# AQCA-Light-Control-uC-A1.net
KiCad netlist of a schematic drawn in Altium Designer
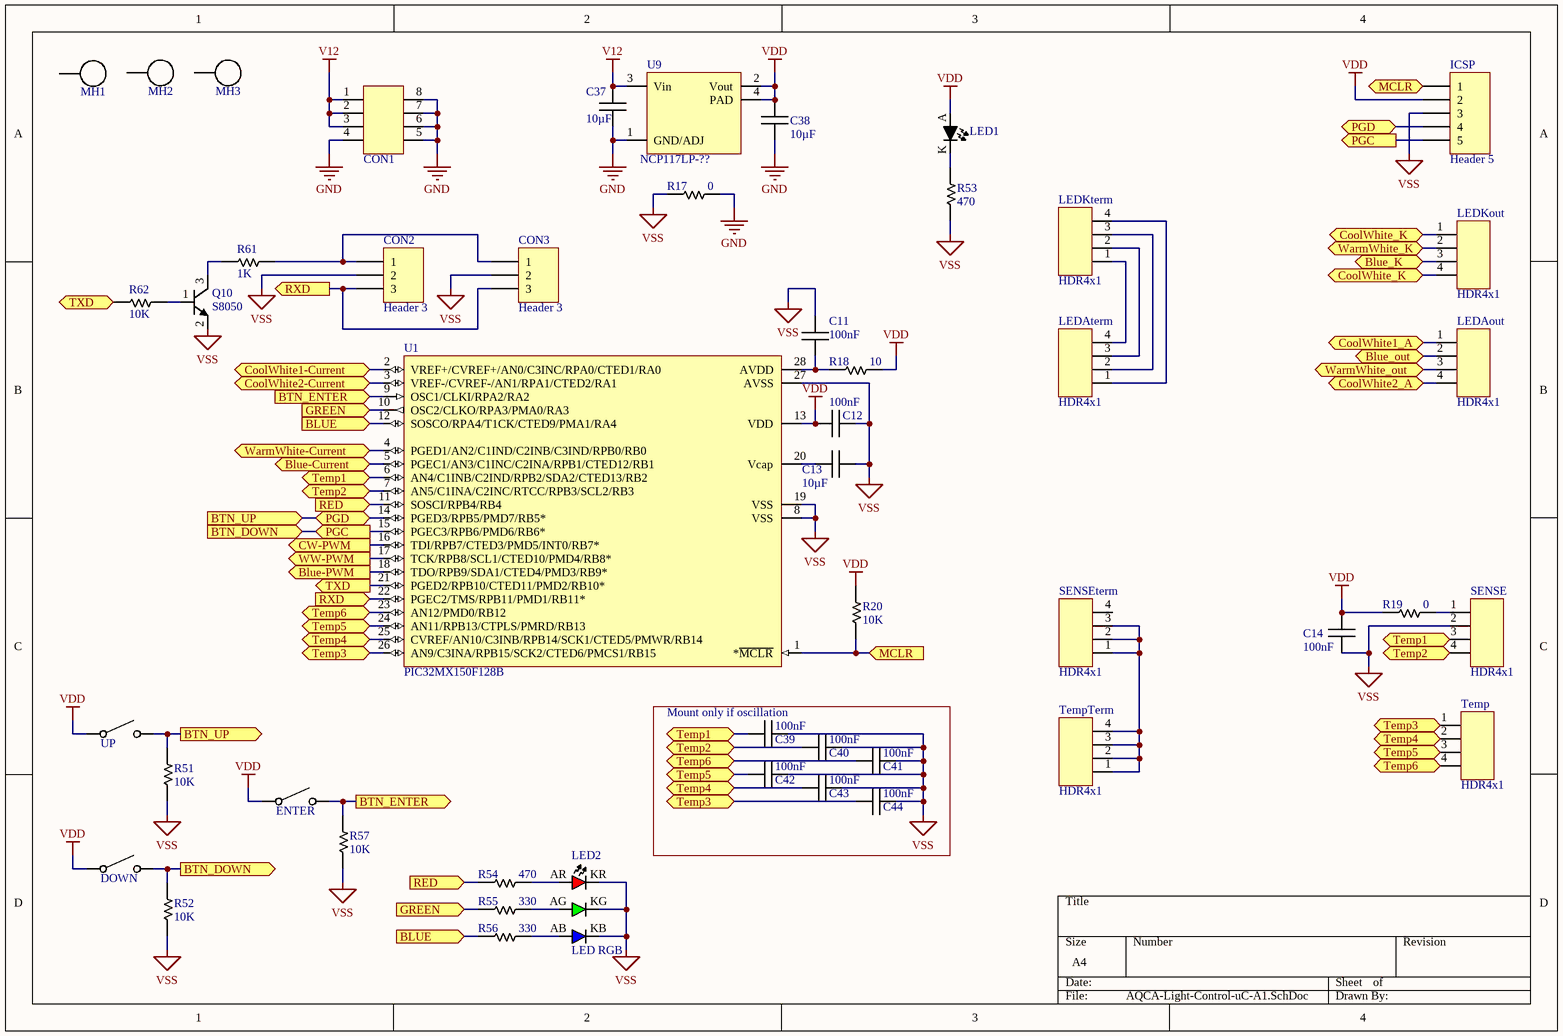
[diagram p0: AQCA-Light-Control-uC-A1.SchDoc]

(export (version "E")
  (design (tool "Eeschema 10.0.6"))
  (components
    (comp (ref "C11")
      (value "100nF")
      (footprint "CAPC1608N")
      (fields (field (name "VOLTAGE") "16V"))
      (libsource (lib "Megaxone") (part "Capacitor"))
    )
    (comp (ref "C12")
      (value "100nF")
      (footprint "CAPC1608N")
      (fields (field (name "VOLTAGE") "16V"))
      (libsource (lib "Megaxone") (part "Capacitor"))
    )
    (comp (ref "C13")
      (value "10µF")
      (footprint "CAPC2012N")
      (fields (field (name "VOLTAGE") "16V"))
      (libsource (lib "Megaxone") (part "Capacitor"))
    )
    (comp (ref "C14")
      (value "100nF")
      (footprint "CAPC1608N")
      (fields (field (name "VOLTAGE") "16V"))
      (libsource (lib "Megaxone") (part "Capacitor"))
    )
    (comp (ref "C37")
      (value "10µF")
      (footprint "CAPC3225N")
      (fields (field (name "VOLTAGE") "25V"))
      (libsource (lib "Megaxone") (part "Capacitor"))
    )
    (comp (ref "C38")
      (value "10µF")
      (footprint "CAPC3225N")
      (fields (field (name "VOLTAGE") "25V"))
      (libsource (lib "Megaxone") (part "Capacitor"))
    )
    (comp (ref "C39")
      (value "100nF")
      (footprint "CAPC1608N")
      (fields (field (name "VOLTAGE") "16V"))
      (libsource (lib "Megaxone") (part "Capacitor"))
    )
    (comp (ref "C40")
      (value "100nF")
      (footprint "CAPC1608N")
      (fields (field (name "VOLTAGE") "16V"))
      (libsource (lib "Megaxone") (part "Capacitor"))
    )
    (comp (ref "C41")
      (value "100nF")
      (footprint "CAPC1608N")
      (fields (field (name "VOLTAGE") "16V"))
      (libsource (lib "Megaxone") (part "Capacitor"))
    )
    (comp (ref "C42")
      (value "100nF")
      (footprint "CAPC1608N")
      (fields (field (name "VOLTAGE") "16V"))
      (libsource (lib "Megaxone") (part "Capacitor"))
    )
    (comp (ref "C43")
      (value "100nF")
      (footprint "CAPC1608N")
      (fields (field (name "VOLTAGE") "16V"))
      (libsource (lib "Megaxone") (part "Capacitor"))
    )
    (comp (ref "C44")
      (value "100nF")
      (footprint "CAPC1608N")
      (fields (field (name "VOLTAGE") "16V"))
      (libsource (lib "Megaxone") (part "Capacitor"))
    )
    (comp (ref "CON1")
      (value "Molex Mini-Fit 8pin")
      (footprint "Molex Mini-Fit 8pin")
      (libsource (lib "Megaxone") (part "Molex Mini-Fit 8pin"))
    )
    (comp (ref "CON2")
      (value "Header 3")
      (footprint "HDR1X3")
      (description "Header, 3-Pin")
      (fields (field (name "PUBLISHER") "Altium Limited"))
      (libsource (lib "Miscellaneous Connectors") (part "Header 3"))
    )
    (comp (ref "CON3")
      (value "Header 3")
      (footprint "HDR1X3")
      (description "Header, 3-Pin")
      (fields (field (name "PUBLISHER") "Altium Limited"))
      (libsource (lib "Miscellaneous Connectors") (part "Header 3"))
    )
    (comp (ref "DOWN")
      (value "Tact Button NO")
      (footprint "TACT SMD 4.5×4.5mm")
      (libsource (lib "Megaxone") (part "Tact Button NO"))
    )
    (comp (ref "ENTER")
      (value "Tact Button NO")
      (footprint "TACT SMD 4.5×4.5mm")
      (libsource (lib "Megaxone") (part "Tact Button NO"))
    )
    (comp (ref "ICSP")
      (value "Header 5")
      (footprint "HDR1X5")
      (description "Header, 5-Pin")
      (fields (field (name "PUBLISHER") "Altium Limited"))
      (libsource (lib "Miscellaneous Connectors") (part "Header 5"))
    )
    (comp (ref "LED1") (value "~") (footprint "LED 3216m") (libsource (lib "Megaxone") (part "LED")))
    (comp (ref "LED2")
      (value "LED RGB")
      (footprint "LED PLCC-6")
      (libsource (lib "Megaxone") (part "LED RGB"))
    )
    (comp (ref "LEDAout")
      (value "HDR4x1")
      (footprint "HDR4x1 EDGE female")
      (libsource (lib "") (part "HDR4x1_1"))
    )
    (comp (ref "LEDAterm")
      (value "HDR4x1")
      (footprint "HDR4x1 EDGE male")
      (libsource (lib "Megaxone") (part "HDR4x1"))
    )
    (comp (ref "LEDKout")
      (value "HDR4x1")
      (footprint "HDR4x1 EDGE female")
      (libsource (lib "") (part "HDR4x1_1"))
    )
    (comp (ref "LEDKterm")
      (value "HDR4x1")
      (footprint "HDR4x1 EDGE male")
      (libsource (lib "Megaxone") (part "HDR4x1"))
    )
    (comp (ref "MH1")
      (value "Mounting Hole")
      (footprint "Mount Hole 4-6.5")
      (libsource (lib "Megaxone") (part "Mounting Hole"))
    )
    (comp (ref "MH2")
      (value "Mounting Hole")
      (footprint "Mount Hole 4-6.5")
      (libsource (lib "Megaxone") (part "Mounting Hole"))
    )
    (comp (ref "MH3")
      (value "Mounting Hole")
      (footprint "Mount Hole 4-6.5")
      (libsource (lib "Megaxone") (part "Mounting Hole"))
    )
    (comp (ref "Q10") (value "S8050") (footprint "SOT23_N") (libsource (lib "Megaxone") (part "NPN")))
    (comp (ref "R17") (value "0") (footprint "RESC1608N") (libsource (lib "Megaxone") (part "Resistor")))
    (comp (ref "R18") (value "10") (footprint "RESC1608N") (libsource (lib "Megaxone") (part "Resistor")))
    (comp (ref "R19") (value "0") (footprint "RESC1608N") (libsource (lib "Megaxone") (part "Resistor")))
    (comp (ref "R20") (value "10K") (footprint "RESC1608N") (libsource (lib "") (part "Resistor_1")))
    (comp (ref "R51") (value "10K") (footprint "RESC1608N") (libsource (lib "") (part "Resistor_1")))
    (comp (ref "R52") (value "10K") (footprint "RESC1608N") (libsource (lib "") (part "Resistor_1")))
    (comp (ref "R53") (value "470") (footprint "RESC1608N") (libsource (lib "") (part "Resistor_1")))
    (comp (ref "R54") (value "470") (footprint "RESC1608N") (libsource (lib "Megaxone") (part "Resistor")))
    (comp (ref "R55") (value "330") (footprint "RESC1608N") (libsource (lib "Megaxone") (part "Resistor")))
    (comp (ref "R56") (value "330") (footprint "RESC1608N") (libsource (lib "Megaxone") (part "Resistor")))
    (comp (ref "R57") (value "10K") (footprint "RESC1608N") (libsource (lib "") (part "Resistor_1")))
    (comp (ref "R61") (value "1K") (footprint "RESC1608N") (libsource (lib "Megaxone") (part "Resistor")))
    (comp (ref "R62") (value "10K") (footprint "RESC1608N") (libsource (lib "Megaxone") (part "Resistor")))
    (comp (ref "SENSE")
      (value "HDR4x1")
      (footprint "HDR4x1 EDGE female")
      (libsource (lib "") (part "HDR4x1_1"))
    )
    (comp (ref "SENSEterm")
      (value "HDR4x1")
      (footprint "HDR4x1 EDGE male")
      (libsource (lib "Megaxone") (part "HDR4x1"))
    )
    (comp (ref "Temp")
      (value "HDR4x1")
      (footprint "HDR4x1 EDGE female")
      (libsource (lib "") (part "HDR4x1_1"))
    )
    (comp (ref "TempTerm")
      (value "HDR4x1")
      (footprint "HDR4x1 EDGE male")
      (libsource (lib "Megaxone") (part "HDR4x1"))
    )
    (comp (ref "U1")
      (value "PIC32MX150F128B")
      (footprint "SSOP28_N")
      (libsource (lib "Megaxone") (part "PIC32MX120FxxxB"))
    )
    (comp (ref "U9")
      (value "NCP117LP-??")
      (footprint "SOT223-4N")
      (libsource (lib "Megaxone") (part "NCP1117LP"))
    )
    (comp (ref "UP")
      (value "Tact Button NO")
      (footprint "TACT SMD 4.5×4.5mm")
      (libsource (lib "Megaxone") (part "Tact Button NO"))
    )
  )
  (nets
    (net (code "1") (name "/BLUE") (class "Default")
      (node (ref "R56") (pin "1") (pinfunction "1_1") (pintype "passive"))
      (node (ref "U1") (pin "12") (pinfunction "SOSCO/RPA4/T1CK/CTED9/PMA1/RA4_12") (pintype "bidirectional"))
    )
    (net (code "2") (name "/BTN_DOWN") (class "Default")
      (node (ref "DOWN") (pin "2") (pinfunction "2_2") (pintype "passive"))
      (node (ref "ICSP") (pin "5") (pinfunction "5_5") (pintype "passive"))
      (node (ref "R52") (pin "2") (pinfunction "2_2") (pintype "passive"))
      (node (ref "U1") (pin "15") (pinfunction "PGEC3/RPB6/PMD6/RB6*_15") (pintype "bidirectional"))
    )
    (net (code "3") (name "/BTN_ENTER") (class "Default")
      (node (ref "ENTER") (pin "2") (pinfunction "2_2") (pintype "passive"))
      (node (ref "R57") (pin "2") (pinfunction "2_2") (pintype "passive"))
      (node (ref "U1") (pin "9") (pinfunction "OSC1/CLKI/RPA2/RA2_9") (pintype "input"))
    )
    (net (code "4") (name "/BTN_UP") (class "Default")
      (node (ref "ICSP") (pin "4") (pinfunction "4_4") (pintype "passive"))
      (node (ref "R51") (pin "2") (pinfunction "2_2") (pintype "passive"))
      (node (ref "U1") (pin "14") (pinfunction "PGED3/RPB5/PMD7/RB5*_14") (pintype "bidirectional"))
      (node (ref "UP") (pin "2") (pinfunction "2_2") (pintype "passive"))
    )
    (net (code "5") (name "/Blue-Current") (class "Default")
      (node (ref "U1") (pin "5") (pinfunction "PGEC1/AN3/C1INC/C2INA/RPB1/CTED12/RB1_5") (pintype "bidirectional"))
    )
    (net (code "6") (name "/Blue-PWM") (class "Default")
      (node (ref "U1") (pin "18") (pinfunction "TDO/RPB9/SDA1/CTED4/PMD3/RB9*_18") (pintype "bidirectional"))
    )
    (net (code "7") (name "/Blue_K") (class "Default")
      (node (ref "LEDKout") (pin "3") (pinfunction "3_3") (pintype "passive"))
    )
    (net (code "8") (name "/Blue_out") (class "Default")
      (node (ref "LEDAout") (pin "2") (pinfunction "2_2") (pintype "passive"))
    )
    (net (code "9") (name "/CW-PWM") (class "Default")
      (node (ref "U1") (pin "16") (pinfunction "TDI/RPB7/CTED3/PMD5/INT0/RB7*_16") (pintype "bidirectional"))
    )
    (net (code "10") (name "/CoolWhite1-Current") (class "Default")
      (node (ref "U1") (pin "2") (pinfunction "VREF+/CVREF+/AN0/C3INC/RPA0/CTED1/RA0_2") (pintype "bidirectional"))
    )
    (net (code "11") (name "/CoolWhite1_A") (class "Default")
      (node (ref "LEDAout") (pin "1") (pinfunction "1_1") (pintype "passive"))
    )
    (net (code "12") (name "/CoolWhite2-Current") (class "Default")
      (node (ref "U1") (pin "3") (pinfunction "VREF-/CVREF-/AN1/RPA1/CTED2/RA1_3") (pintype "bidirectional"))
    )
    (net (code "13") (name "/CoolWhite2_A") (class "Default")
      (node (ref "LEDAout") (pin "4") (pinfunction "4_4") (pintype "passive"))
    )
    (net (code "14") (name "/CoolWhite_K") (class "Default")
      (node (ref "LEDKout") (pin "1") (pinfunction "1_1") (pintype "passive"))
      (node (ref "LEDKout") (pin "4") (pinfunction "4_4") (pintype "passive"))
    )
    (net (code "15") (name "/GREEN") (class "Default")
      (node (ref "R55") (pin "1") (pinfunction "1_1") (pintype "passive"))
      (node (ref "U1") (pin "10") (pinfunction "OSC2/CLKO/RPA3/PMA0/RA3_10") (pintype "output"))
    )
    (net (code "16") (name "/MCLR") (class "Default")
      (node (ref "ICSP") (pin "1") (pinfunction "1_1") (pintype "passive"))
      (node (ref "R20") (pin "1") (pinfunction "1_1") (pintype "passive"))
      (node (ref "U1") (pin "1") (pinfunction "*~{MCLR}_1") (pintype "input"))
    )
    (net (code "17") (name "/RED") (class "Default")
      (node (ref "R54") (pin "1") (pinfunction "1_1") (pintype "passive"))
      (node (ref "U1") (pin "11") (pinfunction "SOSCI/RPB4/RB4_11") (pintype "bidirectional"))
    )
    (net (code "18") (name "/RXD") (class "Default")
      (node (ref "CON2") (pin "3") (pinfunction "3_3") (pintype "passive"))
      (node (ref "CON3") (pin "3") (pinfunction "3_3") (pintype "passive"))
      (node (ref "U1") (pin "22") (pinfunction "PGEC2/TMS/RPB11/PMD1/RB11*_22") (pintype "bidirectional"))
    )
    (net (code "19") (name "/TXD") (class "Default")
      (node (ref "R62") (pin "1") (pinfunction "1_1") (pintype "passive"))
      (node (ref "U1") (pin "21") (pinfunction "PGED2/RPB10/CTED11/PMD2/RB10*_21") (pintype "bidirectional"))
    )
    (net (code "20") (name "/Temp1") (class "Default")
      (node (ref "C39") (pin "1") (pinfunction "1_1") (pintype "passive"))
      (node (ref "SENSE") (pin "3") (pinfunction "3_3") (pintype "passive"))
      (node (ref "U1") (pin "6") (pinfunction "AN4/C1INB/C2IND/RPB2/SDA2/CTED13/RB2_6") (pintype "bidirectional"))
    )
    (net (code "21") (name "/Temp2") (class "Default")
      (node (ref "C40") (pin "1") (pinfunction "1_1") (pintype "passive"))
      (node (ref "SENSE") (pin "4") (pinfunction "4_4") (pintype "passive"))
      (node (ref "U1") (pin "7") (pinfunction "AN5/C1INA/C2INC/RTCC/RPB3/SCL2/RB3_7") (pintype "bidirectional"))
    )
    (net (code "22") (name "/Temp3") (class "Default")
      (node (ref "C44") (pin "1") (pinfunction "1_1") (pintype "passive"))
      (node (ref "Temp") (pin "1") (pinfunction "1_1") (pintype "passive"))
      (node (ref "U1") (pin "26") (pinfunction "AN9/C3INA/RPB15/SCK2/CTED6/PMCS1/RB15_26") (pintype "bidirectional"))
    )
    (net (code "23") (name "/Temp4") (class "Default")
      (node (ref "C43") (pin "1") (pinfunction "1_1") (pintype "passive"))
      (node (ref "Temp") (pin "2") (pinfunction "2_2") (pintype "passive"))
      (node (ref "U1") (pin "25") (pinfunction "CVREF/AN10/C3INB/RPB14/SCK1/CTED5/PMWR/RB14_25") (pintype "bidirectional"))
    )
    (net (code "24") (name "/Temp5") (class "Default")
      (node (ref "C42") (pin "1") (pinfunction "1_1") (pintype "passive"))
      (node (ref "Temp") (pin "3") (pinfunction "3_3") (pintype "passive"))
      (node (ref "U1") (pin "24") (pinfunction "AN11/RPB13/CTPLS/PMRD/RB13_24") (pintype "bidirectional"))
    )
    (net (code "25") (name "/Temp6") (class "Default")
      (node (ref "C41") (pin "1") (pinfunction "1_1") (pintype "passive"))
      (node (ref "Temp") (pin "4") (pinfunction "4_4") (pintype "passive"))
      (node (ref "U1") (pin "23") (pinfunction "AN12/PMD0/RB12_23") (pintype "bidirectional"))
    )
    (net (code "26") (name "/WW-PWM") (class "Default")
      (node (ref "U1") (pin "17") (pinfunction "TCK/RPB8/SCL1/CTED10/PMD4/RB8*_17") (pintype "bidirectional"))
    )
    (net (code "27") (name "/WarmWhite-Current") (class "Default")
      (node (ref "U1") (pin "4") (pinfunction "PGED1/AN2/C1IND/C2INB/C3IND/RPB0/RB0_4") (pintype "bidirectional"))
    )
    (net (code "28") (name "/WarmWhite_K") (class "Default")
      (node (ref "LEDKout") (pin "2") (pinfunction "2_2") (pintype "passive"))
    )
    (net (code "29") (name "/WarmWhite_out") (class "Default")
      (node (ref "LEDAout") (pin "3") (pinfunction "3_3") (pintype "passive"))
    )
    (net (code "30") (name "GND") (class "Default")
      (node (ref "C37") (pin "1") (pinfunction "1_1") (pintype "passive"))
      (node (ref "C38") (pin "1") (pinfunction "1_1") (pintype "passive"))
      (node (ref "CON1") (pin "4") (pintype "power_in"))
      (node (ref "CON1") (pin "5") (pintype "power_in"))
      (node (ref "CON1") (pin "6") (pintype "power_in"))
      (node (ref "CON1") (pin "7") (pintype "power_in"))
      (node (ref "CON1") (pin "8") (pintype "power_in"))
      (node (ref "R17") (pin "2") (pinfunction "2_2") (pintype "passive"))
      (node (ref "U9") (pin "1") (pinfunction "GND/ADJ_1") (pintype "power_in"))
    )
    (net (code "31") (name "Net-(CON2-Pad1)") (class "Default")
      (node (ref "CON2") (pin "1") (pinfunction "1_1") (pintype "passive"))
      (node (ref "CON3") (pin "1") (pinfunction "1_1") (pintype "passive"))
      (node (ref "R61") (pin "2") (pinfunction "2_2") (pintype "passive"))
    )
    (net (code "32") (name "Net-(LED1-PadK)") (class "Default")
      (node (ref "LED1") (pin "K") (pinfunction "K_K") (pintype "passive"))
      (node (ref "R53") (pin "2") (pinfunction "2_2") (pintype "passive"))
    )
    (net (code "33") (name "Net-(LED2-PadAB)") (class "Default")
      (node (ref "LED2") (pin "AB") (pinfunction "AB_AB") (pintype "passive"))
      (node (ref "R56") (pin "2") (pinfunction "2_2") (pintype "passive"))
    )
    (net (code "34") (name "Net-(LED2-PadAG)") (class "Default")
      (node (ref "LED2") (pin "AG") (pinfunction "AG_AG") (pintype "passive"))
      (node (ref "R55") (pin "2") (pinfunction "2_2") (pintype "passive"))
    )
    (net (code "35") (name "Net-(LED2-PadAR)") (class "Default")
      (node (ref "LED2") (pin "AR") (pinfunction "AR_AR") (pintype "passive"))
      (node (ref "R54") (pin "2") (pinfunction "2_2") (pintype "passive"))
    )
    (net (code "36") (name "Net-(LEDAterm-Pad1)") (class "Default")
      (node (ref "LEDAterm") (pin "1") (pinfunction "1_1") (pintype "passive"))
      (node (ref "LEDKterm") (pin "4") (pinfunction "4_4") (pintype "passive"))
    )
    (net (code "37") (name "Net-(LEDAterm-Pad2)") (class "Default")
      (node (ref "LEDAterm") (pin "2") (pinfunction "2_2") (pintype "passive"))
      (node (ref "LEDKterm") (pin "3") (pinfunction "3_3") (pintype "passive"))
    )
    (net (code "38") (name "Net-(LEDAterm-Pad3)") (class "Default")
      (node (ref "LEDAterm") (pin "3") (pinfunction "3_3") (pintype "passive"))
      (node (ref "LEDKterm") (pin "2") (pinfunction "2_2") (pintype "passive"))
    )
    (net (code "39") (name "Net-(LEDAterm-Pad4)") (class "Default")
      (node (ref "LEDAterm") (pin "4") (pinfunction "4_4") (pintype "passive"))
      (node (ref "LEDKterm") (pin "1") (pinfunction "1_1") (pintype "passive"))
    )
    (net (code "40") (name "Net-(Q10-B)") (class "Default")
      (node (ref "Q10") (pin "1") (pinfunction "B_1") (pintype "passive"))
      (node (ref "R62") (pin "2") (pinfunction "2_2") (pintype "passive"))
    )
    (net (code "41") (name "Net-(Q10-C)") (class "Default")
      (node (ref "Q10") (pin "3") (pinfunction "C_3") (pintype "passive"))
      (node (ref "R61") (pin "1") (pinfunction "1_1") (pintype "passive"))
    )
    (net (code "42") (name "Net-(R19-Pad2)") (class "Default")
      (node (ref "R19") (pin "2") (pinfunction "2_2") (pintype "passive"))
      (node (ref "SENSE") (pin "1") (pinfunction "1_1") (pintype "passive"))
    )
    (net (code "43") (name "Net-(SENSEterm-Pad1)") (class "Default")
      (node (ref "SENSEterm") (pin "1") (pinfunction "1_1") (pintype "passive"))
      (node (ref "SENSEterm") (pin "2") (pinfunction "2_2") (pintype "passive"))
      (node (ref "SENSEterm") (pin "3") (pinfunction "3_3") (pintype "passive"))
      (node (ref "TempTerm") (pin "1") (pinfunction "1_1") (pintype "passive"))
      (node (ref "TempTerm") (pin "2") (pinfunction "2_2") (pintype "passive"))
      (node (ref "TempTerm") (pin "3") (pinfunction "3_3") (pintype "passive"))
      (node (ref "TempTerm") (pin "4") (pinfunction "4_4") (pintype "passive"))
    )
    (net (code "44") (name "Net-(U1-AVDD)") (class "Default")
      (node (ref "C11") (pin "1") (pinfunction "1_1") (pintype "passive"))
      (node (ref "R18") (pin "1") (pinfunction "1_1") (pintype "passive"))
      (node (ref "U1") (pin "28") (pinfunction "AVDD_28") (pintype "power_in"))
    )
    (net (code "45") (name "Net-(U1-Vcap)") (class "Default")
      (node (ref "C13") (pin "1") (pinfunction "1_1") (pintype "passive"))
      (node (ref "U1") (pin "20") (pinfunction "Vcap_20") (pintype "power_in"))
    )
    (net (code "46") (name "V12") (class "Default")
      (node (ref "C37") (pin "2") (pinfunction "2_2") (pintype "passive"))
      (node (ref "CON1") (pin "1") (pintype "power_in"))
      (node (ref "CON1") (pin "2") (pintype "power_in"))
      (node (ref "CON1") (pin "3") (pintype "power_in"))
      (node (ref "U9") (pin "3") (pinfunction "Vin_3") (pintype "power_in"))
    )
    (net (code "47") (name "VDD") (class "Default")
      (node (ref "C12") (pin "1") (pinfunction "1_1") (pintype "passive"))
      (node (ref "C14") (pin "2") (pinfunction "2_2") (pintype "passive"))
      (node (ref "C38") (pin "2") (pinfunction "2_2") (pintype "passive"))
      (node (ref "DOWN") (pin "1") (pinfunction "1_1") (pintype "passive"))
      (node (ref "ENTER") (pin "1") (pinfunction "1_1") (pintype "passive"))
      (node (ref "ICSP") (pin "2") (pinfunction "2_2") (pintype "passive"))
      (node (ref "LED1") (pin "A") (pinfunction "A_A") (pintype "passive"))
      (node (ref "R18") (pin "2") (pinfunction "2_2") (pintype "passive"))
      (node (ref "R19") (pin "1") (pinfunction "1_1") (pintype "passive"))
      (node (ref "R20") (pin "2") (pinfunction "2_2") (pintype "passive"))
      (node (ref "U1") (pin "13") (pinfunction "VDD_13") (pintype "power_in"))
      (node (ref "U9") (pin "2") (pinfunction "Vout_2") (pintype "power_in"))
      (node (ref "U9") (pin "4") (pinfunction "PAD_4") (pintype "power_in"))
      (node (ref "UP") (pin "1") (pinfunction "1_1") (pintype "passive"))
    )
    (net (code "48") (name "VSS") (class "Default")
      (node (ref "C11") (pin "2") (pinfunction "2_2") (pintype "passive"))
      (node (ref "C12") (pin "2") (pinfunction "2_2") (pintype "passive"))
      (node (ref "C13") (pin "2") (pinfunction "2_2") (pintype "passive"))
      (node (ref "C14") (pin "1") (pinfunction "1_1") (pintype "passive"))
      (node (ref "C39") (pin "2") (pinfunction "2_2") (pintype "passive"))
      (node (ref "C40") (pin "2") (pinfunction "2_2") (pintype "passive"))
      (node (ref "C41") (pin "2") (pinfunction "2_2") (pintype "passive"))
      (node (ref "C42") (pin "2") (pinfunction "2_2") (pintype "passive"))
      (node (ref "C43") (pin "2") (pinfunction "2_2") (pintype "passive"))
      (node (ref "C44") (pin "2") (pinfunction "2_2") (pintype "passive"))
      (node (ref "CON2") (pin "2") (pinfunction "2_2") (pintype "passive"))
      (node (ref "CON3") (pin "2") (pinfunction "2_2") (pintype "passive"))
      (node (ref "ICSP") (pin "3") (pinfunction "3_3") (pintype "passive"))
      (node (ref "LED2") (pin "KB") (pinfunction "KB_KB") (pintype "passive"))
      (node (ref "LED2") (pin "KG") (pinfunction "KG_KG") (pintype "passive"))
      (node (ref "LED2") (pin "KR") (pinfunction "KR_KR") (pintype "passive"))
      (node (ref "Q10") (pin "2") (pinfunction "E_2") (pintype "passive"))
      (node (ref "R17") (pin "1") (pinfunction "1_1") (pintype "passive"))
      (node (ref "R51") (pin "1") (pinfunction "1_1") (pintype "passive"))
      (node (ref "R52") (pin "1") (pinfunction "1_1") (pintype "passive"))
      (node (ref "R53") (pin "1") (pinfunction "1_1") (pintype "passive"))
      (node (ref "R57") (pin "1") (pinfunction "1_1") (pintype "passive"))
      (node (ref "SENSE") (pin "2") (pinfunction "2_2") (pintype "passive"))
      (node (ref "U1") (pin "19") (pinfunction "VSS_19") (pintype "power_in"))
      (node (ref "U1") (pin "27") (pinfunction "AVSS_27") (pintype "power_in"))
      (node (ref "U1") (pin "8") (pinfunction "VSS_8") (pintype "power_in"))
    )
    (net (code "49") (name "unconnected-(MH1-Pad1)") (class "Default")
      (node (ref "MH1") (pin "1") (pintype "power_in"))
    )
    (net (code "50") (name "unconnected-(MH2-Pad1)") (class "Default")
      (node (ref "MH2") (pin "1") (pintype "power_in"))
    )
    (net (code "51") (name "unconnected-(MH3-Pad1)") (class "Default")
      (node (ref "MH3") (pin "1") (pintype "power_in"))
    )
    (net (code "52") (name "unconnected-(SENSEterm-Pad4)") (class "Default")
      (node (ref "SENSEterm") (pin "4") (pinfunction "4_4") (pintype "passive"))
    )
  )
)
